# 3_UART.net
KiCad netlist of a schematic drawn in Altium Designer
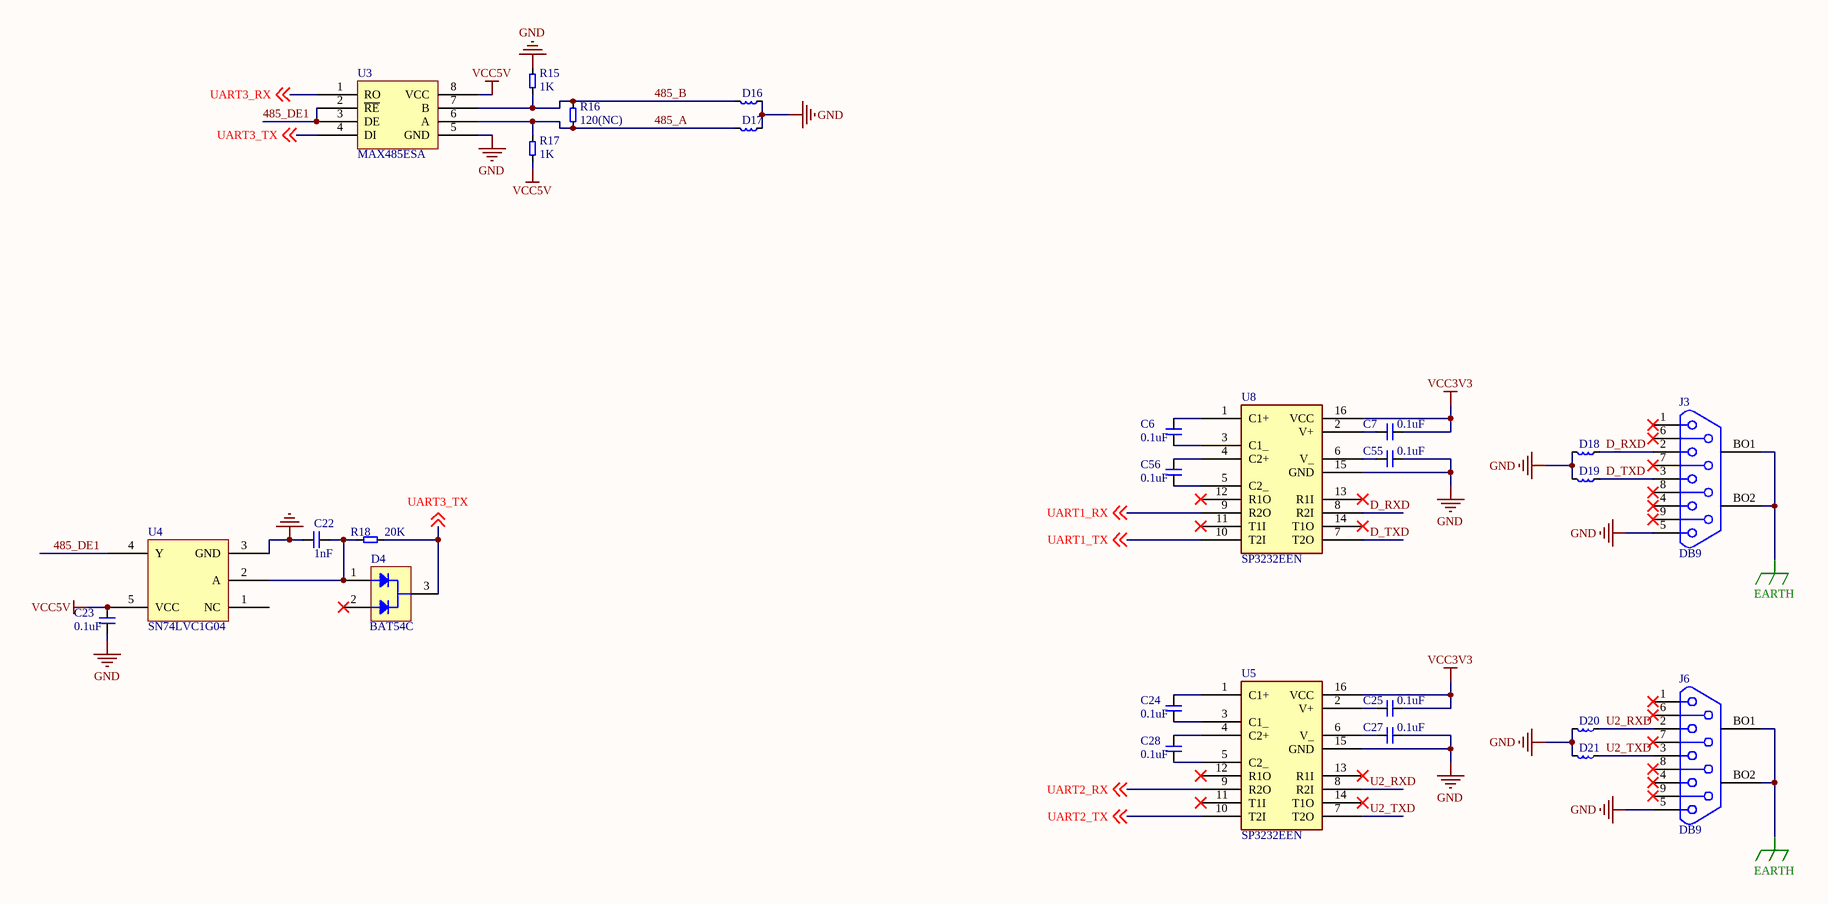
[diagram p0: 3.UART.SchDoc]

(export (version "E")
  (design (tool "Eeschema 10.0.6"))
  (components
    (comp (ref "C6")
      (value "0.1uF")
      (footprint "0603C")
      (description "电容")
      (libsource (lib "LDT-SCH") (part "电容"))
    )
    (comp (ref "C7")
      (value "0.1uF")
      (footprint "0603C")
      (description "电容")
      (libsource (lib "LDT-SCH") (part "电容"))
    )
    (comp (ref "C22") (value "1nF") (footprint "0603C") (description "电容") (libsource (lib "*") (part "电容")))
    (comp (ref "C23")
      (value "0.1uF")
      (footprint "0603C")
      (description "电容")
      (libsource (lib "LDT-SCH") (part "电容"))
    )
    (comp (ref "C24")
      (value "0.1uF")
      (footprint "0603C")
      (description "电容")
      (libsource (lib "LDT-SCH") (part "电容"))
    )
    (comp (ref "C25")
      (value "0.1uF")
      (footprint "0603C")
      (description "电容")
      (libsource (lib "LDT-SCH") (part "电容"))
    )
    (comp (ref "C27")
      (value "0.1uF")
      (footprint "0603C")
      (description "电容")
      (libsource (lib "LDT-SCH") (part "电容"))
    )
    (comp (ref "C28")
      (value "0.1uF")
      (footprint "0603C")
      (description "电容")
      (libsource (lib "LDT-SCH") (part "电容"))
    )
    (comp (ref "C55")
      (value "0.1uF")
      (footprint "0603C")
      (description "电容")
      (libsource (lib "LDT-SCH") (part "电容"))
    )
    (comp (ref "C56")
      (value "0.1uF")
      (footprint "0603C")
      (description "电容")
      (libsource (lib "LDT-SCH") (part "电容"))
    )
    (comp (ref "D4")
      (value "BAT54C")
      (footprint "SOT-23")
      (description "SCHOTTKY DIODE")
      (libsource (lib "LDT-SCH") (part "BAT54C"))
    )
    (comp (ref "D16") (value "ESD") (footprint "0603L") (libsource (lib "LDT-SCH") (part "电感")))
    (comp (ref "D17") (value "ESD") (footprint "0603L") (libsource (lib "LDT-SCH") (part "电感")))
    (comp (ref "D18") (value "ESD") (footprint "0603L") (libsource (lib "LDT-SCH") (part "电感")))
    (comp (ref "D19") (value "ESD") (footprint "0603L") (libsource (lib "LDT-SCH") (part "电感")))
    (comp (ref "D20") (value "ESD") (footprint "0603L") (libsource (lib "LDT-SCH") (part "电感")))
    (comp (ref "D21") (value "ESD") (footprint "0603L") (libsource (lib "LDT-SCH") (part "电感")))
    (comp (ref "J3") (value "DB9") (footprint "DB-9/M") (libsource (lib "LDT-SCH") (part "DB9")))
    (comp (ref "J6") (value "DB9") (footprint "DB-9/M") (libsource (lib "LDT-SCH") (part "DB9")))
    (comp (ref "R15")
      (value "1K")
      (footprint "0603R")
      (description "电阻")
      (libsource (lib "LDT-SCH") (part "电阻"))
    )
    (comp (ref "R16")
      (value "120(NC)")
      (footprint "0603R")
      (description "电阻")
      (libsource (lib "LDT-SCH") (part "电阻"))
    )
    (comp (ref "R17")
      (value "1K")
      (footprint "0603R")
      (description "电阻")
      (libsource (lib "LDT-SCH") (part "电阻"))
    )
    (comp (ref "R18") (value "20K") (footprint "0603R") (description "电阻") (libsource (lib "*") (part "电阻")))
    (comp (ref "U3")
      (value "MAX485ESA")
      (footprint "SOP8-1.27")
      (libsource (lib "LDT-SCH") (part "MAX485ESA"))
    )
    (comp (ref "U4")
      (value "SN74LVC1G04")
      (footprint "SOT23-5N")
      (libsource (lib "Tank") (part "SN74LVC1G04"))
    )
    (comp (ref "U5")
      (value "SP3232EEN")
      (footprint "SOIC16-1.27")
      (libsource (lib "LDT-SCH") (part "MAX232ESE"))
    )
    (comp (ref "U8")
      (value "SP3232EEN")
      (footprint "SOIC16-1.27")
      (libsource (lib "LDT-SCH") (part "MAX232ESE"))
    )
  )
  (nets
    (net (code "1") (name "/485_A") (class "Default")
      (node (ref "D17") (pin "2") (pintype "passive"))
      (node (ref "R16") (pin "1") (pintype "passive"))
      (node (ref "R17") (pin "2") (pintype "passive"))
      (node (ref "U3") (pin "6") (pinfunction "A_6") (pintype "passive"))
    )
    (net (code "2") (name "/485_B") (class "Default")
      (node (ref "D16") (pin "2") (pintype "passive"))
      (node (ref "R15") (pin "1") (pintype "passive"))
      (node (ref "R16") (pin "2") (pintype "passive"))
      (node (ref "U3") (pin "7") (pinfunction "B_7") (pintype "passive"))
    )
    (net (code "3") (name "/485_DE1") (class "Default")
      (node (ref "U3") (pin "2") (pinfunction "~{RE}_2") (pintype "passive"))
      (node (ref "U3") (pin "3") (pinfunction "DE_3") (pintype "passive"))
      (node (ref "U4") (pin "4") (pinfunction "Y_4") (pintype "passive"))
    )
    (net (code "4") (name "/D_RXD") (class "Default")
      (node (ref "D18") (pin "1") (pintype "passive"))
      (node (ref "J3") (pin "2") (pinfunction "2_2") (pintype "passive"))
      (node (ref "U8") (pin "8") (pinfunction "R2I_8") (pintype "passive"))
    )
    (net (code "5") (name "/D_TXD") (class "Default")
      (node (ref "D19") (pin "1") (pintype "passive"))
      (node (ref "J3") (pin "3") (pinfunction "3_3") (pintype "passive"))
      (node (ref "U8") (pin "7") (pinfunction "T2O_7") (pintype "passive"))
    )
    (net (code "6") (name "/U2_RXD") (class "Default")
      (node (ref "D20") (pin "1") (pintype "passive"))
      (node (ref "J6") (pin "2") (pinfunction "2_2") (pintype "passive"))
      (node (ref "U5") (pin "8") (pinfunction "R2I_8") (pintype "passive"))
    )
    (net (code "7") (name "/U2_TXD") (class "Default")
      (node (ref "D21") (pin "1") (pintype "passive"))
      (node (ref "J6") (pin "3") (pinfunction "3_3") (pintype "passive"))
      (node (ref "U5") (pin "7") (pinfunction "T2O_7") (pintype "passive"))
    )
    (net (code "8") (name "EARTH") (class "Default")
      (node (ref "J3") (pin "BO1") (pinfunction "BO1_BO1") (pintype "passive"))
      (node (ref "J3") (pin "BO2") (pinfunction "BO2_BO2") (pintype "passive"))
      (node (ref "J6") (pin "BO1") (pinfunction "BO1_BO1") (pintype "passive"))
      (node (ref "J6") (pin "BO2") (pinfunction "BO2_BO2") (pintype "passive"))
    )
    (net (code "9") (name "GND") (class "Default")
      (node (ref "C22") (pin "1") (pintype "passive"))
      (node (ref "C23") (pin "2") (pintype "passive"))
      (node (ref "C27") (pin "2") (pintype "passive"))
      (node (ref "C55") (pin "2") (pintype "passive"))
      (node (ref "D16") (pin "1") (pintype "passive"))
      (node (ref "D17") (pin "1") (pintype "passive"))
      (node (ref "D18") (pin "2") (pintype "passive"))
      (node (ref "D19") (pin "2") (pintype "passive"))
      (node (ref "D20") (pin "2") (pintype "passive"))
      (node (ref "D21") (pin "2") (pintype "passive"))
      (node (ref "J3") (pin "5") (pinfunction "5_5") (pintype "passive"))
      (node (ref "J6") (pin "5") (pinfunction "5_5") (pintype "passive"))
      (node (ref "R15") (pin "2") (pintype "passive"))
      (node (ref "U3") (pin "5") (pinfunction "GND_5") (pintype "passive"))
      (node (ref "U4") (pin "3") (pinfunction "GND_3") (pintype "passive"))
      (node (ref "U5") (pin "15") (pinfunction "GND_15") (pintype "passive"))
      (node (ref "U8") (pin "15") (pinfunction "GND_15") (pintype "passive"))
    )
    (net (code "10") (name "Net-(U4-A)") (class "Default")
      (node (ref "C22") (pin "2") (pintype "passive"))
      (node (ref "D4") (pin "1") (pinfunction "1_1") (pintype "passive"))
      (node (ref "R18") (pin "1") (pintype "passive"))
      (node (ref "U4") (pin "2") (pinfunction "A_2") (pintype "passive"))
    )
    (net (code "11") (name "Net-(U5-C1+)") (class "Default")
      (node (ref "C24") (pin "1") (pintype "passive"))
      (node (ref "U5") (pin "1") (pinfunction "C1+_1") (pintype "passive"))
    )
    (net (code "12") (name "Net-(U5-C1_)") (class "Default")
      (node (ref "C24") (pin "2") (pintype "passive"))
      (node (ref "U5") (pin "3") (pinfunction "C1__3") (pintype "passive"))
    )
    (net (code "13") (name "Net-(U5-C2+)") (class "Default")
      (node (ref "C28") (pin "1") (pintype "passive"))
      (node (ref "U5") (pin "4") (pinfunction "C2+_4") (pintype "passive"))
    )
    (net (code "14") (name "Net-(U5-C2_)") (class "Default")
      (node (ref "C28") (pin "2") (pintype "passive"))
      (node (ref "U5") (pin "5") (pinfunction "C2__5") (pintype "passive"))
    )
    (net (code "15") (name "Net-(U5-V+)") (class "Default")
      (node (ref "C25") (pin "1") (pintype "passive"))
      (node (ref "U5") (pin "2") (pinfunction "V+_2") (pintype "passive"))
    )
    (net (code "16") (name "Net-(U5-V_)") (class "Default")
      (node (ref "C27") (pin "1") (pintype "passive"))
      (node (ref "U5") (pin "6") (pinfunction "V__6") (pintype "passive"))
    )
    (net (code "17") (name "Net-(U8-C1+)") (class "Default")
      (node (ref "C6") (pin "1") (pintype "passive"))
      (node (ref "U8") (pin "1") (pinfunction "C1+_1") (pintype "passive"))
    )
    (net (code "18") (name "Net-(U8-C1_)") (class "Default")
      (node (ref "C6") (pin "2") (pintype "passive"))
      (node (ref "U8") (pin "3") (pinfunction "C1__3") (pintype "passive"))
    )
    (net (code "19") (name "Net-(U8-C2+)") (class "Default")
      (node (ref "C56") (pin "1") (pintype "passive"))
      (node (ref "U8") (pin "4") (pinfunction "C2+_4") (pintype "passive"))
    )
    (net (code "20") (name "Net-(U8-C2_)") (class "Default")
      (node (ref "C56") (pin "2") (pintype "passive"))
      (node (ref "U8") (pin "5") (pinfunction "C2__5") (pintype "passive"))
    )
    (net (code "21") (name "Net-(U8-V+)") (class "Default")
      (node (ref "C7") (pin "1") (pintype "passive"))
      (node (ref "U8") (pin "2") (pinfunction "V+_2") (pintype "passive"))
    )
    (net (code "22") (name "Net-(U8-V_)") (class "Default")
      (node (ref "C55") (pin "1") (pintype "passive"))
      (node (ref "U8") (pin "6") (pinfunction "V__6") (pintype "passive"))
    )
    (net (code "23") (name "UART1_RX") (class "Default")
      (node (ref "U8") (pin "9") (pinfunction "R2O_9") (pintype "passive"))
    )
    (net (code "24") (name "UART1_TX") (class "Default")
      (node (ref "U8") (pin "10") (pinfunction "T2I_10") (pintype "passive"))
    )
    (net (code "25") (name "UART2_RX") (class "Default")
      (node (ref "U5") (pin "9") (pinfunction "R2O_9") (pintype "passive"))
    )
    (net (code "26") (name "UART2_TX") (class "Default")
      (node (ref "U5") (pin "10") (pinfunction "T2I_10") (pintype "passive"))
    )
    (net (code "27") (name "UART3_RX") (class "Default")
      (node (ref "U3") (pin "1") (pinfunction "RO_1") (pintype "passive"))
    )
    (net (code "28") (name "UART3_TX") (class "Default")
      (node (ref "D4") (pin "3") (pinfunction "3_3") (pintype "passive"))
      (node (ref "R18") (pin "2") (pintype "passive"))
      (node (ref "U3") (pin "4") (pinfunction "DI_4") (pintype "passive"))
    )
    (net (code "29") (name "VCC3V3") (class "Default")
      (node (ref "C25") (pin "2") (pintype "passive"))
      (node (ref "C7") (pin "2") (pintype "passive"))
      (node (ref "U5") (pin "16") (pinfunction "VCC_16") (pintype "passive"))
      (node (ref "U8") (pin "16") (pinfunction "VCC_16") (pintype "passive"))
    )
    (net (code "30") (name "VCC5V") (class "Default")
      (node (ref "C23") (pin "1") (pintype "passive"))
      (node (ref "R17") (pin "1") (pintype "passive"))
      (node (ref "U3") (pin "8") (pinfunction "VCC_8") (pintype "passive"))
      (node (ref "U4") (pin "5") (pinfunction "VCC_5") (pintype "passive"))
    )
    (net (code "31") (name "unconnected-(D4-Pad2)") (class "Default")
      (node (ref "D4") (pin "2") (pinfunction "2_2") (pintype "passive+no_connect"))
    )
    (net (code "32") (name "unconnected-(J3-Pad1)") (class "Default")
      (node (ref "J3") (pin "1") (pinfunction "1_1") (pintype "passive+no_connect"))
    )
    (net (code "33") (name "unconnected-(J3-Pad4)") (class "Default")
      (node (ref "J3") (pin "4") (pinfunction "4_4") (pintype "passive+no_connect"))
    )
    (net (code "34") (name "unconnected-(J3-Pad6)") (class "Default")
      (node (ref "J3") (pin "6") (pinfunction "6_6") (pintype "passive+no_connect"))
    )
    (net (code "35") (name "unconnected-(J3-Pad7)") (class "Default")
      (node (ref "J3") (pin "7") (pinfunction "7_7") (pintype "passive+no_connect"))
    )
    (net (code "36") (name "unconnected-(J3-Pad8)") (class "Default")
      (node (ref "J3") (pin "8") (pinfunction "8_8") (pintype "passive+no_connect"))
    )
    (net (code "37") (name "unconnected-(J3-Pad9)") (class "Default")
      (node (ref "J3") (pin "9") (pinfunction "9_9") (pintype "passive+no_connect"))
    )
    (net (code "38") (name "unconnected-(J6-Pad1)") (class "Default")
      (node (ref "J6") (pin "1") (pinfunction "1_1") (pintype "passive+no_connect"))
    )
    (net (code "39") (name "unconnected-(J6-Pad4)") (class "Default")
      (node (ref "J6") (pin "4") (pinfunction "4_4") (pintype "passive+no_connect"))
    )
    (net (code "40") (name "unconnected-(J6-Pad6)") (class "Default")
      (node (ref "J6") (pin "6") (pinfunction "6_6") (pintype "passive+no_connect"))
    )
    (net (code "41") (name "unconnected-(J6-Pad7)") (class "Default")
      (node (ref "J6") (pin "7") (pinfunction "7_7") (pintype "passive+no_connect"))
    )
    (net (code "42") (name "unconnected-(J6-Pad8)") (class "Default")
      (node (ref "J6") (pin "8") (pinfunction "8_8") (pintype "passive+no_connect"))
    )
    (net (code "43") (name "unconnected-(J6-Pad9)") (class "Default")
      (node (ref "J6") (pin "9") (pinfunction "9_9") (pintype "passive+no_connect"))
    )
    (net (code "44") (name "unconnected-(U4-NC-Pad1)") (class "Default")
      (node (ref "U4") (pin "1") (pinfunction "NC_1") (pintype "passive"))
    )
    (net (code "45") (name "unconnected-(U5-R1I-Pad13)") (class "Default")
      (node (ref "U5") (pin "13") (pinfunction "R1I_13") (pintype "passive+no_connect"))
    )
    (net (code "46") (name "unconnected-(U5-R1O-Pad12)") (class "Default")
      (node (ref "U5") (pin "12") (pinfunction "R1O_12") (pintype "passive+no_connect"))
    )
    (net (code "47") (name "unconnected-(U5-T1I-Pad11)") (class "Default")
      (node (ref "U5") (pin "11") (pinfunction "T1I_11") (pintype "passive+no_connect"))
    )
    (net (code "48") (name "unconnected-(U5-T1O-Pad14)") (class "Default")
      (node (ref "U5") (pin "14") (pinfunction "T1O_14") (pintype "passive+no_connect"))
    )
    (net (code "49") (name "unconnected-(U8-R1I-Pad13)") (class "Default")
      (node (ref "U8") (pin "13") (pinfunction "R1I_13") (pintype "passive+no_connect"))
    )
    (net (code "50") (name "unconnected-(U8-R1O-Pad12)") (class "Default")
      (node (ref "U8") (pin "12") (pinfunction "R1O_12") (pintype "passive+no_connect"))
    )
    (net (code "51") (name "unconnected-(U8-T1I-Pad11)") (class "Default")
      (node (ref "U8") (pin "11") (pinfunction "T1I_11") (pintype "passive+no_connect"))
    )
    (net (code "52") (name "unconnected-(U8-T1O-Pad14)") (class "Default")
      (node (ref "U8") (pin "14") (pinfunction "T1O_14") (pintype "passive+no_connect"))
    )
  )
)
